# oled_control.net
KiCad netlist of a schematic drawn in Altium Designer
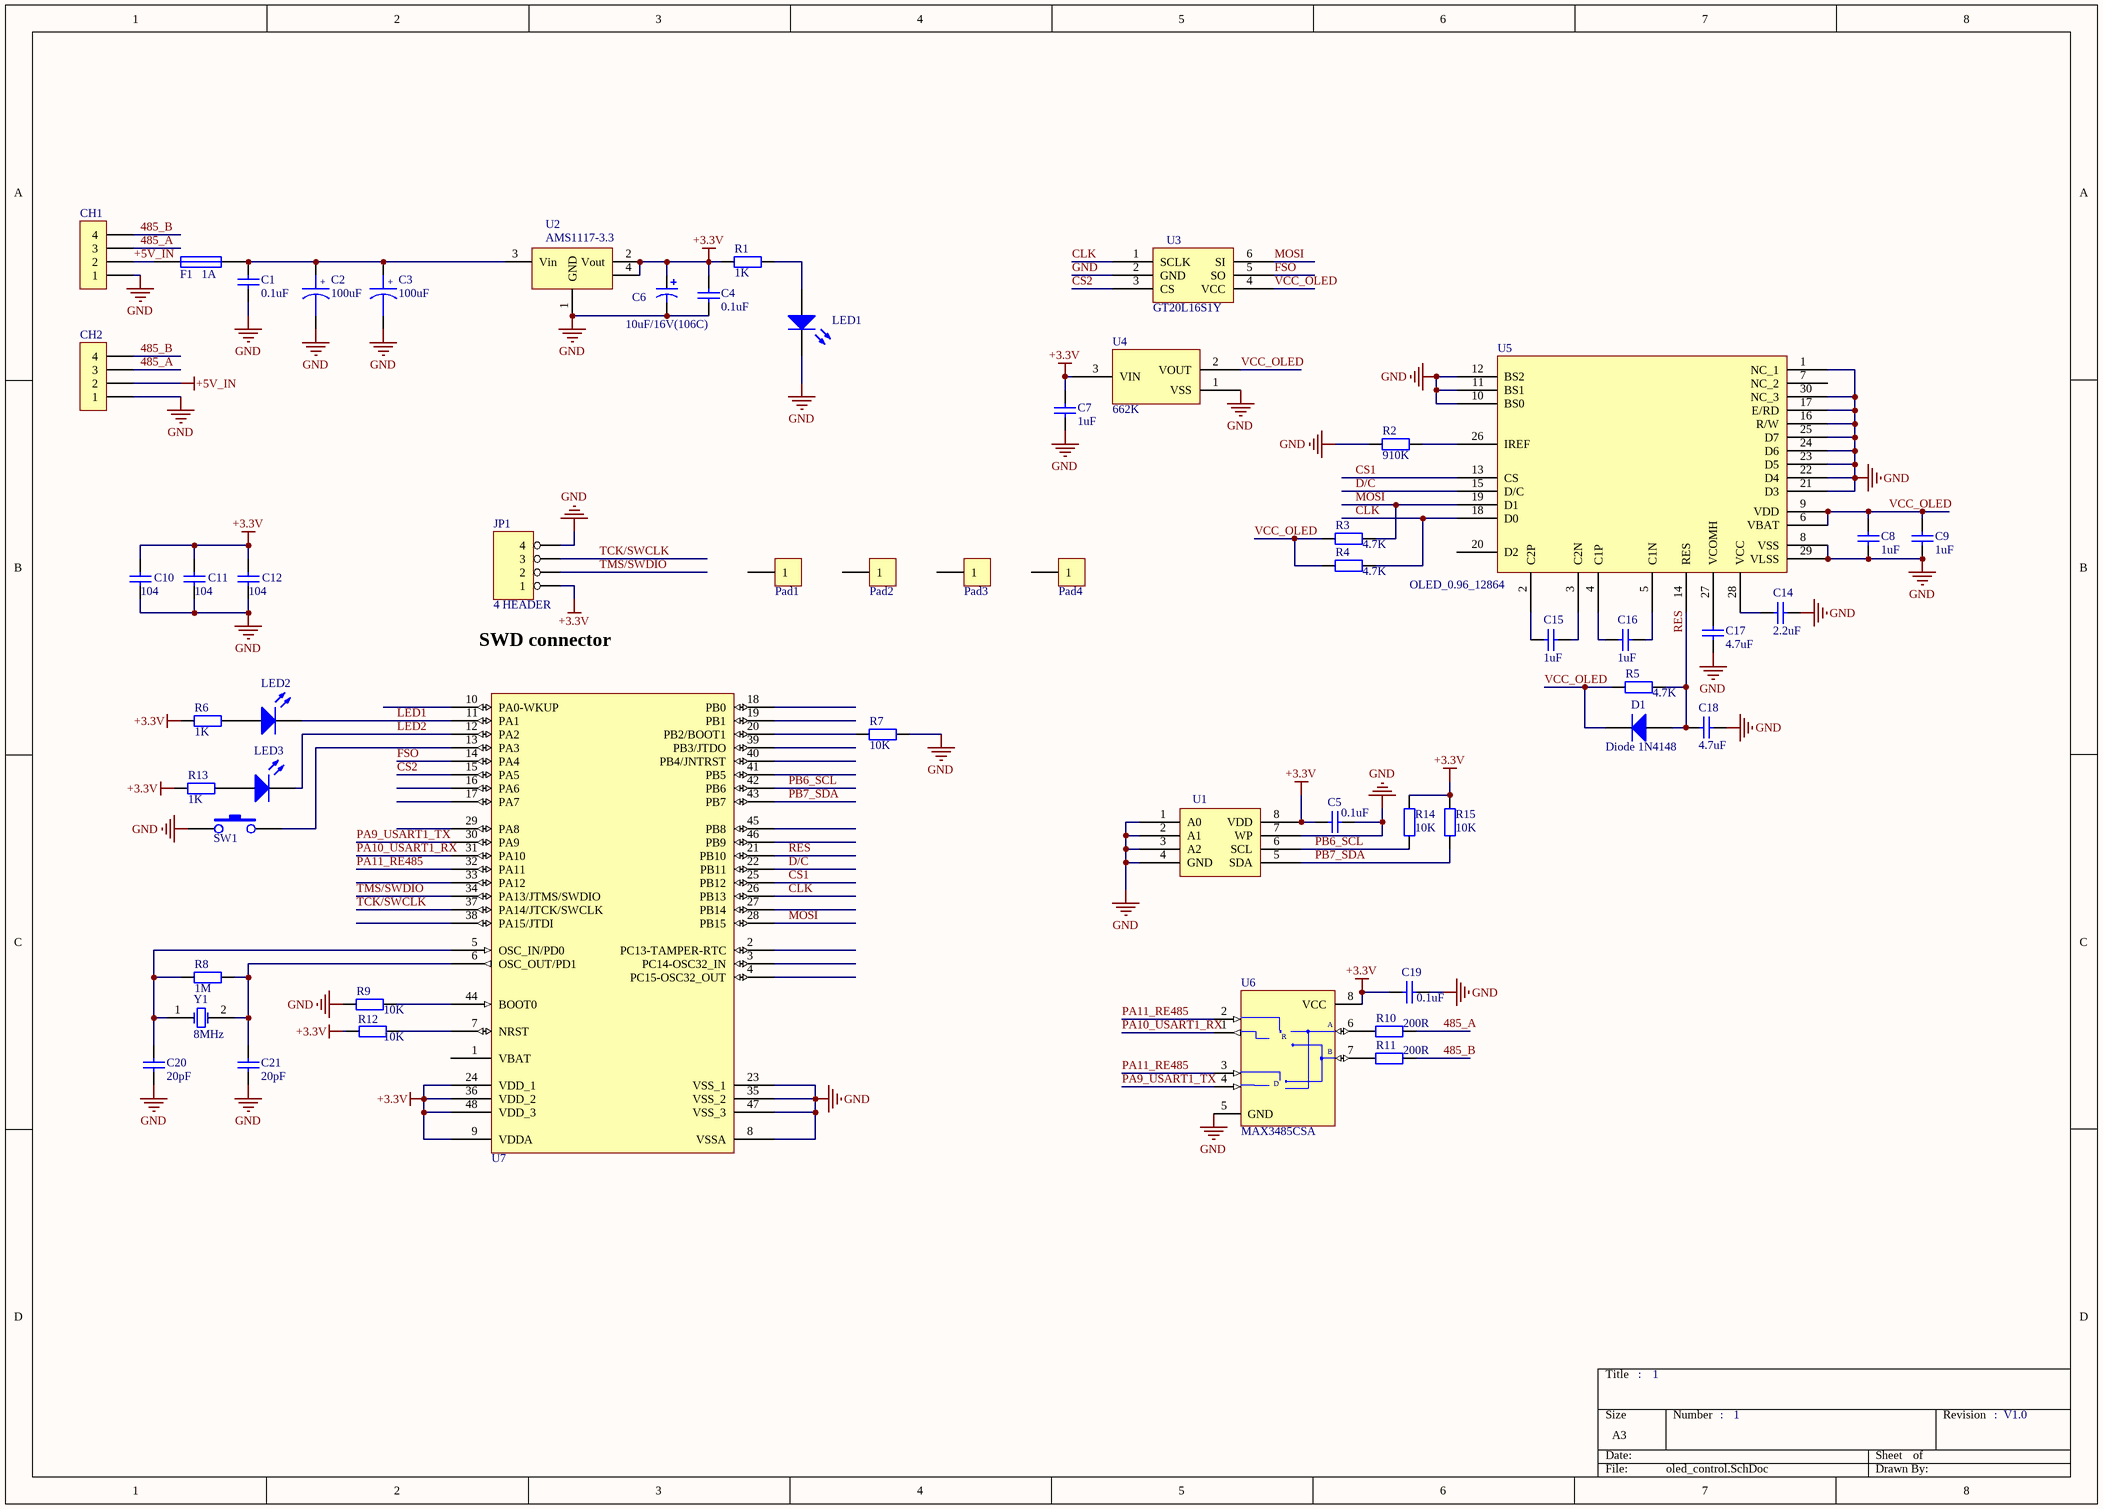
[diagram p0: oled_control.SchDoc]

(export (version "E")
  (design (tool "Eeschema 10.0.6"))
  (components
    (comp (ref "C1")
      (value "0.1uF")
      (footprint "0805")
      (description "Capacitor")
      (fields (field (name "Comment") "Cap") (field (name "PUBLISHER") "Altium Limited"))
      (libsource (lib "Miscellaneous Devices") (part "Cap"))
    )
    (comp (ref "C2")
      (value "C_2200uF")
      (footprint "B: 3528")
      (fields (field (name "ALTIUM_UNNAMED_1") "100uF"))
      (libsource (lib "myIntegrated_Library1") (part "C_2200uF"))
    )
    (comp (ref "C3")
      (value "C_2200uF")
      (footprint "B: 3528")
      (fields (field (name "ALTIUM_UNNAMED_1") "100uF"))
      (libsource (lib "myIntegrated_Library1") (part "C_2200uF"))
    )
    (comp (ref "C4")
      (value "0.1uF")
      (footprint "0805")
      (description "Capacitor")
      (fields (field (name "Comment") "Cap") (field (name "PUBLISHER") "Altium Limited"))
      (libsource (lib "Miscellaneous Devices") (part "Cap"))
    )
    (comp (ref "C5")
      (value "0.1uF")
      (footprint "0805")
      (description "Capacitor")
      (fields (field (name "Comment") "Cap") (field (name "PUBLISHER") "Altium Limited"))
      (libsource (lib "Miscellaneous Devices") (part "Cap"))
    )
    (comp (ref "C6")
      (value "10uF/16V(106C)")
      (footprint "CAP A-3216")
      (description "Polarized Capacitor (Surface Mount)")
      (fields (field (name "Comment") "Cap Pol3") (field (name "PUBLISHER") "Altium Limited"))
      (libsource (lib "Miscellaneous Devices") (part "Cap Pol3"))
    )
    (comp (ref "C7")
      (value "1uF")
      (footprint "0805")
      (description "Capacitor")
      (fields (field (name "Comment") "Cap") (field (name "PUBLISHER") "Altium Limited"))
      (libsource (lib "Miscellaneous Devices") (part "Cap"))
    )
    (comp (ref "C8")
      (value "1uF")
      (footprint "0805")
      (description "Capacitor")
      (fields (field (name "Comment") "Cap") (field (name "PUBLISHER") "Altium Limited"))
      (libsource (lib "Miscellaneous Devices") (part "Cap"))
    )
    (comp (ref "C9")
      (value "1uF")
      (footprint "0805")
      (description "Capacitor")
      (fields (field (name "Comment") "Cap") (field (name "PUBLISHER") "Altium Limited"))
      (libsource (lib "Miscellaneous Devices") (part "Cap"))
    )
    (comp (ref "C10")
      (value "104")
      (footprint "0805")
      (description "Capacitor")
      (fields (field (name "Comment") "Cap") (field (name "PUBLISHER") "Altium Limited"))
      (libsource (lib "Miscellaneous Devices") (part "Cap"))
    )
    (comp (ref "C11")
      (value "104")
      (footprint "0805")
      (description "Capacitor")
      (fields (field (name "Comment") "Cap") (field (name "PUBLISHER") "Altium Limited"))
      (libsource (lib "Miscellaneous Devices") (part "Cap"))
    )
    (comp (ref "C12")
      (value "104")
      (footprint "0805")
      (description "Capacitor")
      (fields (field (name "Comment") "Cap") (field (name "PUBLISHER") "Altium Limited"))
      (libsource (lib "Miscellaneous Devices") (part "Cap"))
    )
    (comp (ref "C14")
      (value "2.2uF")
      (footprint "0805")
      (description "Capacitor")
      (fields (field (name "Comment") "Cap") (field (name "PUBLISHER") "Altium Limited"))
      (libsource (lib "Miscellaneous Devices") (part "Cap"))
    )
    (comp (ref "C15")
      (value "1uF")
      (footprint "0805")
      (description "Capacitor")
      (fields (field (name "Comment") "Cap") (field (name "PUBLISHER") "Altium Limited"))
      (libsource (lib "Miscellaneous Devices") (part "Cap"))
    )
    (comp (ref "C16")
      (value "1uF")
      (footprint "0805")
      (description "Capacitor")
      (fields (field (name "Comment") "Cap") (field (name "PUBLISHER") "Altium Limited"))
      (libsource (lib "Miscellaneous Devices") (part "Cap"))
    )
    (comp (ref "C17")
      (value "4.7uF")
      (footprint "0805")
      (description "Capacitor")
      (fields (field (name "Comment") "Cap") (field (name "PUBLISHER") "Altium Limited"))
      (libsource (lib "Miscellaneous Devices") (part "Cap"))
    )
    (comp (ref "C18")
      (value "4.7uF")
      (footprint "0805")
      (description "Capacitor")
      (fields (field (name "Comment") "Cap") (field (name "PUBLISHER") "Altium Limited"))
      (libsource (lib "Miscellaneous Devices") (part "Cap"))
    )
    (comp (ref "C19")
      (value "0.1uF")
      (footprint "0805")
      (description "Capacitor")
      (fields (field (name "Comment") "Cap") (field (name "PUBLISHER") "Altium Limited"))
      (libsource (lib "Miscellaneous Devices") (part "Cap"))
    )
    (comp (ref "C20")
      (value "20pF")
      (footprint "0805")
      (description "Capacitor")
      (fields (field (name "Comment") "Cap") (field (name "PUBLISHER") "Altium Limited"))
      (libsource (lib "开发板元件库") (part "Cap"))
    )
    (comp (ref "C21")
      (value "20pF")
      (footprint "0805")
      (description "Capacitor")
      (fields (field (name "Comment") "Cap") (field (name "PUBLISHER") "Altium Limited"))
      (libsource (lib "开发板元件库") (part "Cap"))
    )
    (comp (ref "CH1")
      (value "HEADER1X4")
      (footprint "CON4_1.5")
      (libsource (lib "myIntegrated_Library1") (part "HEADER1X4"))
    )
    (comp (ref "CH2")
      (value "HEADER1X4")
      (footprint "CON4_1.5")
      (libsource (lib "myIntegrated_Library1") (part "HEADER1X4"))
    )
    (comp (ref "D1")
      (value "Diode 1N4148")
      (footprint "LL34")
      (description "High Conductance Fast Diode")
      (fields (field (name "PUBLISHER") "Altium Limited"))
      (libsource (lib "Miscellaneous Devices") (part "Diode 1N4148"))
    )
    (comp (ref "F1")
      (value "FUSE")
      (footprint "0805")
      (fields (field (name "ALTIUM_UNNAMED_1") "1A"))
      (libsource (lib "myIntegrated_Library1") (part "FUSE"))
    )
    (comp (ref "JP1")
      (value "4 HEADER")
      (footprint "CON4_1.5")
      (description "4 Pin Header")
      (libsource (lib "Miscellaneous Devices") (part "4 HEADER"))
    )
    (comp (ref "LED1")
      (value "~")
      (footprint "LED-0805")
      (description "Typical RED, GREEN, YELLOW, AMBER GaAs LED")
      (fields (field (name "PUBLISHER") "Altium Limited"))
      (libsource (lib "Miscellaneous Devices") (part "LED2"))
    )
    (comp (ref "LED2")
      (value "~")
      (footprint "LED-0805")
      (description "Typical RED, GREEN, YELLOW, AMBER GaAs LED")
      (fields (field (name "PUBLISHER") "Altium Limited"))
      (libsource (lib "Miscellaneous Devices") (part "LED2"))
    )
    (comp (ref "LED3")
      (value "~")
      (footprint "LED_5X5")
      (description "Typical RED, GREEN, YELLOW, AMBER GaAs LED")
      (fields (field (name "PUBLISHER") "Altium Limited"))
      (libsource (lib "Miscellaneous Devices") (part "LED2"))
    )
    (comp (ref "Pad1")
      (value "Pad")
      (footprint "pad35")
      (libsource (lib "myIntegrated_Library1") (part "Pad"))
    )
    (comp (ref "Pad2")
      (value "Pad")
      (footprint "pad35")
      (libsource (lib "myIntegrated_Library1") (part "Pad"))
    )
    (comp (ref "Pad3")
      (value "Pad")
      (footprint "pad35")
      (libsource (lib "myIntegrated_Library1") (part "Pad"))
    )
    (comp (ref "Pad4")
      (value "Pad")
      (footprint "pad35")
      (libsource (lib "myIntegrated_Library1") (part "Pad"))
    )
    (comp (ref "R1")
      (value "1K")
      (footprint "0805")
      (description "Resistor")
      (fields (field (name "Comment") "Res2") (field (name "PUBLISHER") "Altium Limited"))
      (libsource (lib "Miscellaneous Devices") (part "Res2"))
    )
    (comp (ref "R2")
      (value "910K")
      (footprint "0805")
      (description "Resistor")
      (fields (field (name "Comment") "Res2") (field (name "PUBLISHER") "Altium Limited"))
      (libsource (lib "Miscellaneous Devices") (part "Res2"))
    )
    (comp (ref "R3")
      (value "4.7K")
      (footprint "0805")
      (description "Resistor")
      (fields (field (name "Comment") "Res2") (field (name "PUBLISHER") "Altium Limited"))
      (libsource (lib "Miscellaneous Devices") (part "Res2"))
    )
    (comp (ref "R4")
      (value "4.7K")
      (footprint "0805")
      (description "Resistor")
      (fields (field (name "Comment") "Res2") (field (name "PUBLISHER") "Altium Limited"))
      (libsource (lib "Miscellaneous Devices") (part "Res2"))
    )
    (comp (ref "R5")
      (value "4.7K")
      (footprint "0805")
      (description "Resistor")
      (fields (field (name "Comment") "Res2") (field (name "PUBLISHER") "Altium Limited"))
      (libsource (lib "Miscellaneous Devices") (part "Res2"))
    )
    (comp (ref "R6")
      (value "1K")
      (footprint "0805")
      (description "Resistor")
      (fields (field (name "Comment") "Res2") (field (name "PUBLISHER") "Altium Limited"))
      (libsource (lib "Miscellaneous Devices") (part "Res2"))
    )
    (comp (ref "R7")
      (value "10K")
      (footprint "0805")
      (description "Resistor")
      (fields (field (name "Comment") "Res2") (field (name "PUBLISHER") "Altium Limited"))
      (libsource (lib "开发板元件库") (part "Res2"))
    )
    (comp (ref "R8")
      (value "1M")
      (footprint "0805")
      (description "Resistor")
      (fields (field (name "Comment") "Res2") (field (name "PUBLISHER") "Altium Limited"))
      (libsource (lib "开发板元件库") (part "Res2"))
    )
    (comp (ref "R9")
      (value "10K")
      (footprint "0805")
      (description "Resistor")
      (fields (field (name "Comment") "Res2") (field (name "PUBLISHER") "Altium Limited"))
      (libsource (lib "开发板元件库") (part "Res2"))
    )
    (comp (ref "R10")
      (value "200R")
      (footprint "0805")
      (description "Resistor")
      (fields (field (name "Comment") "Res2") (field (name "PUBLISHER") "Altium Limited"))
      (libsource (lib "") (part "Res2_1"))
    )
    (comp (ref "R11")
      (value "200R")
      (footprint "0805")
      (description "Resistor")
      (fields (field (name "Comment") "Res2") (field (name "PUBLISHER") "Altium Limited"))
      (libsource (lib "") (part "Res2_1"))
    )
    (comp (ref "R12")
      (value "10K")
      (footprint "0805")
      (description "Resistor")
      (fields (field (name "Comment") "Res2") (field (name "PUBLISHER") "Altium Limited"))
      (libsource (lib "开发板元件库") (part "Res2"))
    )
    (comp (ref "R13")
      (value "1K")
      (footprint "0805")
      (description "Resistor")
      (fields (field (name "Comment") "Res2") (field (name "PUBLISHER") "Altium Limited"))
      (libsource (lib "Miscellaneous Devices") (part "Res2"))
    )
    (comp (ref "R14")
      (value "10K")
      (footprint "C0805tan")
      (description "Resistor")
      (fields (field (name "Comment") "Res2") (field (name "PUBLISHER") "Altium Limited"))
      (libsource (lib "") (part "Res2_2"))
    )
    (comp (ref "R15")
      (value "10K")
      (footprint "C0805tan")
      (description "Resistor")
      (fields (field (name "Comment") "Res2") (field (name "PUBLISHER") "Altium Limited"))
      (libsource (lib "") (part "Res2_2"))
    )
    (comp (ref "SW1")
      (value "SW-KEY-2")
      (footprint "KEY_SOP4X4")
      (libsource (lib "myIntegrated_Library1") (part "SW-KEY-2"))
    )
    (comp (ref "U1")
      (value "AT24c02")
      (footprint "TSSOP8")
      (libsource (lib "myIntegrated_Library1") (part "TI24c02"))
    )
    (comp (ref "U2")
      (value "AMS1117-3.3")
      (footprint "SOT223")
      (libsource (lib "货架电子标签元件库") (part "AMS1117-5"))
    )
    (comp (ref "U3")
      (value "GT20L16S1Y")
      (footprint "SOT23-6")
      (libsource (lib "myIntegrated_Library1") (part "GT20L16S1Y"))
    )
    (comp (ref "U4")
      (value "662K")
      (footprint "SOT-23")
      (libsource (lib "myIntegrated_Library1") (part "662K"))
    )
    (comp (ref "U5")
      (value "OLED_0.96_12864")
      (footprint "OLED_1.30_12864")
      (libsource (lib "myIntegrated_Library1") (part "OLED_0.96_12864"))
    )
    (comp (ref "U6")
      (value "MAX3485CSA")
      (footprint "NS08-L")
      (libsource (lib "myIntegrated_Library1") (part "MAX485CSA"))
    )
    (comp (ref "U7")
      (value "STM32F103C8T6")
      (footprint "LQFP48")
      (libsource (lib "myIntegrated_Library1") (part "STM32F103C8T6"))
    )
    (comp (ref "Y1")
      (value "8MHz")
      (footprint "XTAL_US1")
      (description "Crystal Oscillator")
      (fields (field (name "PUBLISHER") "Altium Limited"))
      (libsource (lib "战舰STM32开发板底板封装库") (part "XTAL"))
    )
  )
  (nets
    (net (code "1") (name "+3.3V") (class "Default")
      (node (ref "C10") (pin "2") (pinfunction "2_2") (pintype "passive"))
      (node (ref "C11") (pin "2") (pinfunction "2_2") (pintype "passive"))
      (node (ref "C12") (pin "2") (pinfunction "2_2") (pintype "passive"))
      (node (ref "C19") (pin "1") (pinfunction "1_1") (pintype "passive"))
      (node (ref "C4") (pin "2") (pinfunction "2_2") (pintype "passive"))
      (node (ref "C5") (pin "2") (pinfunction "2_2") (pintype "passive"))
      (node (ref "C6") (pin "1") (pinfunction "1_1") (pintype "passive"))
      (node (ref "C7") (pin "1") (pinfunction "1_1") (pintype "passive"))
      (node (ref "JP1") (pin "1") (pinfunction "1_1") (pintype "passive"))
      (node (ref "R1") (pin "2") (pinfunction "2_2") (pintype "passive"))
      (node (ref "R12") (pin "1") (pinfunction "1_1") (pintype "passive"))
      (node (ref "R13") (pin "2") (pinfunction "2_2") (pintype "passive"))
      (node (ref "R14") (pin "2") (pinfunction "2_2") (pintype "passive"))
      (node (ref "R15") (pin "2") (pinfunction "2_2") (pintype "passive"))
      (node (ref "R6") (pin "2") (pinfunction "2_2") (pintype "passive"))
      (node (ref "U1") (pin "8") (pinfunction "VDD_8") (pintype "passive"))
      (node (ref "U2") (pin "2") (pinfunction "Vout_2") (pintype "passive"))
      (node (ref "U2") (pin "4") (pintype "passive"))
      (node (ref "U4") (pin "3") (pinfunction "VIN_3") (pintype "passive"))
      (node (ref "U6") (pin "8") (pinfunction "VCC_8") (pintype "power_in"))
      (node (ref "U7") (pin "24") (pinfunction "VDD_1_24") (pintype "power_in"))
      (node (ref "U7") (pin "36") (pinfunction "VDD_2_36") (pintype "power_in"))
      (node (ref "U7") (pin "48") (pinfunction "VDD_3_48") (pintype "power_in"))
      (node (ref "U7") (pin "9") (pinfunction "VDDA_9") (pintype "power_in"))
    )
    (net (code "2") (name "+5V_IN") (class "Default")
      (node (ref "CH1") (pin "2") (pinfunction "2_2") (pintype "passive"))
      (node (ref "CH2") (pin "2") (pinfunction "2_2") (pintype "passive"))
      (node (ref "F1") (pin "1") (pinfunction "1_1") (pintype "passive"))
    )
    (net (code "3") (name "/485_A") (class "Default")
      (node (ref "CH1") (pin "3") (pinfunction "3_3") (pintype "passive"))
      (node (ref "CH2") (pin "3") (pinfunction "3_3") (pintype "passive"))
      (node (ref "R10") (pin "2") (pinfunction "2_2") (pintype "passive"))
    )
    (net (code "4") (name "/485_B") (class "Default")
      (node (ref "CH1") (pin "4") (pinfunction "4_4") (pintype "passive"))
      (node (ref "CH2") (pin "4") (pinfunction "4_4") (pintype "passive"))
      (node (ref "R11") (pin "2") (pinfunction "2_2") (pintype "passive"))
    )
    (net (code "5") (name "/CLK") (class "Default")
      (node (ref "R4") (pin "1") (pinfunction "1_1") (pintype "passive"))
      (node (ref "U3") (pin "1") (pinfunction "SCLK_1") (pintype "passive"))
      (node (ref "U5") (pin "18") (pinfunction "D0_18") (pintype "passive"))
      (node (ref "U7") (pin "26") (pinfunction "PB13_26") (pintype "bidirectional"))
    )
    (net (code "6") (name "/CS1") (class "Default")
      (node (ref "U5") (pin "13") (pinfunction "CS_13") (pintype "passive"))
      (node (ref "U7") (pin "25") (pinfunction "PB12_25") (pintype "bidirectional"))
    )
    (net (code "7") (name "/CS2") (class "Default")
      (node (ref "U3") (pin "3") (pinfunction "CS_3") (pintype "passive"))
      (node (ref "U7") (pin "15") (pinfunction "PA5_15") (pintype "bidirectional"))
    )
    (net (code "8") (name "/D{slash}C") (class "Default")
      (node (ref "U5") (pin "15") (pinfunction "D/C_15") (pintype "passive"))
      (node (ref "U7") (pin "22") (pinfunction "PB11_22") (pintype "bidirectional"))
    )
    (net (code "9") (name "/FSO") (class "Default")
      (node (ref "U3") (pin "5") (pinfunction "SO_5") (pintype "passive"))
      (node (ref "U7") (pin "14") (pinfunction "PA4_14") (pintype "bidirectional"))
    )
    (net (code "10") (name "/LED1") (class "Default")
      (node (ref "LED2") (pin "2") (pinfunction "K_2") (pintype "passive"))
      (node (ref "U7") (pin "11") (pinfunction "PA1_11") (pintype "bidirectional"))
    )
    (net (code "11") (name "/LED2") (class "Default")
      (node (ref "LED3") (pin "2") (pinfunction "K_2") (pintype "passive"))
      (node (ref "U7") (pin "12") (pinfunction "PA2_12") (pintype "bidirectional"))
    )
    (net (code "12") (name "/MOSI") (class "Default")
      (node (ref "R3") (pin "1") (pinfunction "1_1") (pintype "passive"))
      (node (ref "U3") (pin "6") (pinfunction "SI_6") (pintype "passive"))
      (node (ref "U5") (pin "19") (pinfunction "D1_19") (pintype "passive"))
      (node (ref "U7") (pin "28") (pinfunction "PB15_28") (pintype "bidirectional"))
    )
    (net (code "13") (name "/PA9_USART1_TX") (class "Default")
      (node (ref "U6") (pin "4") (pinfunction "DI_4") (pintype "input"))
      (node (ref "U7") (pin "30") (pinfunction "PA9_30") (pintype "bidirectional"))
    )
    (net (code "14") (name "/PA10_USART1_RX") (class "Default")
      (node (ref "U6") (pin "1") (pinfunction "RO_1") (pintype "output"))
      (node (ref "U7") (pin "31") (pinfunction "PA10_31") (pintype "bidirectional"))
    )
    (net (code "15") (name "/PA11_RE485") (class "Default")
      (node (ref "U6") (pin "2") (pinfunction "~{RE}_2") (pintype "input"))
      (node (ref "U6") (pin "3") (pinfunction "DE_3") (pintype "input"))
      (node (ref "U7") (pin "32") (pinfunction "PA11_32") (pintype "bidirectional"))
    )
    (net (code "16") (name "/PB6_SCL") (class "Default")
      (node (ref "R14") (pin "1") (pinfunction "1_1") (pintype "passive"))
      (node (ref "U1") (pin "6") (pinfunction "SCL_6") (pintype "passive"))
      (node (ref "U7") (pin "42") (pinfunction "PB6_42") (pintype "bidirectional"))
    )
    (net (code "17") (name "/PB7_SDA") (class "Default")
      (node (ref "R15") (pin "1") (pinfunction "1_1") (pintype "passive"))
      (node (ref "U1") (pin "5") (pinfunction "SDA_5") (pintype "passive"))
      (node (ref "U7") (pin "43") (pinfunction "PB7_43") (pintype "bidirectional"))
    )
    (net (code "18") (name "/RES") (class "Default")
      (node (ref "C18") (pin "2") (pinfunction "2_2") (pintype "passive"))
      (node (ref "D1") (pin "1") (pinfunction "A_1") (pintype "passive"))
      (node (ref "R5") (pin "1") (pinfunction "1_1") (pintype "passive"))
      (node (ref "U5") (pin "14") (pinfunction "RES_14") (pintype "passive"))
      (node (ref "U7") (pin "21") (pinfunction "PB10_21") (pintype "bidirectional"))
    )
    (net (code "19") (name "/TCK{slash}SWCLK") (class "Default")
      (node (ref "JP1") (pin "3") (pinfunction "3_3") (pintype "passive"))
      (node (ref "U7") (pin "37") (pinfunction "PA14/JTCK/SWCLK_37") (pintype "bidirectional"))
    )
    (net (code "20") (name "/TMS{slash}SWDIO") (class "Default")
      (node (ref "JP1") (pin "2") (pinfunction "2_2") (pintype "passive"))
      (node (ref "U7") (pin "34") (pinfunction "PA13/JTMS/SWDIO_34") (pintype "bidirectional"))
    )
    (net (code "21") (name "/VCC_OLED") (class "Default")
      (node (ref "C8") (pin "1") (pinfunction "1_1") (pintype "passive"))
      (node (ref "C9") (pin "1") (pinfunction "1_1") (pintype "passive"))
      (node (ref "D1") (pin "2") (pinfunction "K_2") (pintype "passive"))
      (node (ref "R3") (pin "2") (pinfunction "2_2") (pintype "passive"))
      (node (ref "R4") (pin "2") (pinfunction "2_2") (pintype "passive"))
      (node (ref "R5") (pin "2") (pinfunction "2_2") (pintype "passive"))
      (node (ref "U3") (pin "4") (pinfunction "VCC_4") (pintype "passive"))
      (node (ref "U4") (pin "2") (pinfunction "VOUT_2") (pintype "passive"))
      (node (ref "U5") (pin "6") (pinfunction "VBAT_6") (pintype "passive"))
      (node (ref "U5") (pin "9") (pinfunction "VDD_9") (pintype "passive"))
    )
    (net (code "22") (name "GND") (class "Default")
      (node (ref "C1") (pin "1") (pinfunction "1_1") (pintype "passive"))
      (node (ref "C10") (pin "1") (pinfunction "1_1") (pintype "passive"))
      (node (ref "C11") (pin "1") (pinfunction "1_1") (pintype "passive"))
      (node (ref "C12") (pin "1") (pinfunction "1_1") (pintype "passive"))
      (node (ref "C14") (pin "1") (pinfunction "1_1") (pintype "passive"))
      (node (ref "C17") (pin "2") (pinfunction "2_2") (pintype "passive"))
      (node (ref "C18") (pin "1") (pinfunction "1_1") (pintype "passive"))
      (node (ref "C19") (pin "2") (pinfunction "2_2") (pintype "passive"))
      (node (ref "C2") (pin "2") (pinfunction "2_2") (pintype "passive"))
      (node (ref "C20") (pin "1") (pinfunction "1_1") (pintype "passive"))
      (node (ref "C21") (pin "1") (pinfunction "1_1") (pintype "passive"))
      (node (ref "C3") (pin "2") (pinfunction "2_2") (pintype "passive"))
      (node (ref "C4") (pin "1") (pinfunction "1_1") (pintype "passive"))
      (node (ref "C5") (pin "1") (pinfunction "1_1") (pintype "passive"))
      (node (ref "C6") (pin "2") (pinfunction "2_2") (pintype "passive"))
      (node (ref "C7") (pin "2") (pinfunction "2_2") (pintype "passive"))
      (node (ref "C8") (pin "2") (pinfunction "2_2") (pintype "passive"))
      (node (ref "C9") (pin "2") (pinfunction "2_2") (pintype "passive"))
      (node (ref "CH1") (pin "1") (pinfunction "1_1") (pintype "passive"))
      (node (ref "CH2") (pin "1") (pinfunction "1_1") (pintype "passive"))
      (node (ref "JP1") (pin "4") (pinfunction "4_4") (pintype "passive"))
      (node (ref "LED1") (pin "2") (pinfunction "K_2") (pintype "passive"))
      (node (ref "R2") (pin "2") (pinfunction "2_2") (pintype "passive"))
      (node (ref "R7") (pin "2") (pinfunction "2_2") (pintype "passive"))
      (node (ref "R9") (pin "1") (pinfunction "1_1") (pintype "passive"))
      (node (ref "SW1") (pin "1") (pinfunction "1_1") (pintype "passive"))
      (node (ref "U1") (pin "1") (pinfunction "A0_1") (pintype "passive"))
      (node (ref "U1") (pin "2") (pinfunction "A1_2") (pintype "passive"))
      (node (ref "U1") (pin "3") (pinfunction "A2_3") (pintype "passive"))
      (node (ref "U1") (pin "4") (pinfunction "GND_4") (pintype "passive"))
      (node (ref "U1") (pin "7") (pinfunction "WP_7") (pintype "passive"))
      (node (ref "U2") (pin "1") (pinfunction "GND_1") (pintype "passive"))
      (node (ref "U3") (pin "2") (pinfunction "GND_2") (pintype "passive"))
      (node (ref "U4") (pin "1") (pinfunction "VSS_1") (pintype "passive"))
      (node (ref "U5") (pin "1") (pinfunction "NC_1_1") (pintype "passive"))
      (node (ref "U5") (pin "10") (pinfunction "BS0_10") (pintype "passive"))
      (node (ref "U5") (pin "11") (pinfunction "BS1_11") (pintype "passive"))
      (node (ref "U5") (pin "12") (pinfunction "BS2_12") (pintype "passive"))
      (node (ref "U5") (pin "16") (pinfunction "R/W_16") (pintype "passive"))
      (node (ref "U5") (pin "17") (pinfunction "E/RD_17") (pintype "passive"))
      (node (ref "U5") (pin "21") (pinfunction "D3_21") (pintype "passive"))
      (node (ref "U5") (pin "22") (pinfunction "D4_22") (pintype "passive"))
      (node (ref "U5") (pin "23") (pinfunction "D5_23") (pintype "passive"))
      (node (ref "U5") (pin "24") (pinfunction "D6_24") (pintype "passive"))
      (node (ref "U5") (pin "25") (pinfunction "D7_25") (pintype "passive"))
      (node (ref "U5") (pin "29") (pinfunction "VLSS_29") (pintype "passive"))
      (node (ref "U5") (pin "30") (pinfunction "NC_3_30") (pintype "passive"))
      (node (ref "U5") (pin "8") (pinfunction "VSS_8") (pintype "passive"))
      (node (ref "U6") (pin "5") (pinfunction "GND_5") (pintype "power_in"))
      (node (ref "U7") (pin "23") (pinfunction "VSS_1_23") (pintype "power_in"))
      (node (ref "U7") (pin "35") (pinfunction "VSS_2_35") (pintype "power_in"))
      (node (ref "U7") (pin "47") (pinfunction "VSS_3_47") (pintype "power_in"))
      (node (ref "U7") (pin "8") (pinfunction "VSSA_8") (pintype "power_in"))
    )
    (net (code "23") (name "Net-(LED1-A)") (class "Default")
      (node (ref "LED1") (pin "1") (pinfunction "A_1") (pintype "passive"))
      (node (ref "R1") (pin "1") (pinfunction "1_1") (pintype "passive"))
    )
    (net (code "24") (name "Net-(LED2-A)") (class "Default")
      (node (ref "LED2") (pin "1") (pinfunction "A_1") (pintype "passive"))
      (node (ref "R6") (pin "1") (pinfunction "1_1") (pintype "passive"))
    )
    (net (code "25") (name "Net-(LED3-A)") (class "Default")
      (node (ref "LED3") (pin "1") (pinfunction "A_1") (pintype "passive"))
      (node (ref "R13") (pin "1") (pinfunction "1_1") (pintype "passive"))
    )
    (net (code "26") (name "Net-(U2-Vin)") (class "Default")
      (node (ref "C1") (pin "2") (pinfunction "2_2") (pintype "passive"))
      (node (ref "C2") (pin "1") (pinfunction "1_1") (pintype "passive"))
      (node (ref "C3") (pin "1") (pinfunction "1_1") (pintype "passive"))
      (node (ref "F1") (pin "2") (pinfunction "2_2") (pintype "passive"))
      (node (ref "U2") (pin "3") (pinfunction "Vin_3") (pintype "passive"))
    )
    (net (code "27") (name "Net-(U5-C1N)") (class "Default")
      (node (ref "C16") (pin "1") (pinfunction "1_1") (pintype "passive"))
      (node (ref "U5") (pin "5") (pinfunction "C1N_5") (pintype "passive"))
    )
    (net (code "28") (name "Net-(U5-C1P)") (class "Default")
      (node (ref "C16") (pin "2") (pinfunction "2_2") (pintype "passive"))
      (node (ref "U5") (pin "4") (pinfunction "C1P_4") (pintype "passive"))
    )
    (net (code "29") (name "Net-(U5-C2N)") (class "Default")
      (node (ref "C15") (pin "1") (pinfunction "1_1") (pintype "passive"))
      (node (ref "U5") (pin "3") (pinfunction "C2N_3") (pintype "passive"))
    )
    (net (code "30") (name "Net-(U5-C2P)") (class "Default")
      (node (ref "C15") (pin "2") (pinfunction "2_2") (pintype "passive"))
      (node (ref "U5") (pin "2") (pinfunction "C2P_2") (pintype "passive"))
    )
    (net (code "31") (name "Net-(U5-IREF)") (class "Default")
      (node (ref "R2") (pin "1") (pinfunction "1_1") (pintype "passive"))
      (node (ref "U5") (pin "26") (pinfunction "IREF_26") (pintype "passive"))
    )
    (net (code "32") (name "Net-(U5-VCC)") (class "Default")
      (node (ref "C14") (pin "2") (pinfunction "2_2") (pintype "passive"))
      (node (ref "U5") (pin "28") (pinfunction "VCC_28") (pintype "passive"))
    )
    (net (code "33") (name "Net-(U5-VCOMH)") (class "Default")
      (node (ref "C17") (pin "1") (pinfunction "1_1") (pintype "passive"))
      (node (ref "U5") (pin "27") (pinfunction "VCOMH_27") (pintype "passive"))
    )
    (net (code "34") (name "Net-(U6-A)") (class "Default")
      (node (ref "R10") (pin "1") (pinfunction "1_1") (pintype "passive"))
      (node (ref "U6") (pin "6") (pinfunction "A_6") (pintype "bidirectional"))
    )
    (net (code "35") (name "Net-(U6-B)") (class "Default")
      (node (ref "R11") (pin "1") (pinfunction "1_1") (pintype "passive"))
      (node (ref "U6") (pin "7") (pinfunction "B_7") (pintype "bidirectional"))
    )
    (net (code "36") (name "Net-(U7-BOOT0)") (class "Default")
      (node (ref "R9") (pin "2") (pinfunction "2_2") (pintype "passive"))
      (node (ref "U7") (pin "44") (pinfunction "BOOT0_44") (pintype "input"))
    )
    (net (code "37") (name "Net-(U7-NRST)") (class "Default")
      (node (ref "R12") (pin "2") (pinfunction "2_2") (pintype "passive"))
      (node (ref "U7") (pin "7") (pinfunction "NRST_7") (pintype "bidirectional"))
    )
    (net (code "38") (name "Net-(U7-OSC_IN{slash}PD0)") (class "Default")
      (node (ref "C20") (pin "2") (pinfunction "2_2") (pintype "passive"))
      (node (ref "R8") (pin "1") (pinfunction "1_1") (pintype "passive"))
      (node (ref "U7") (pin "5") (pinfunction "OSC_IN/PD0_5") (pintype "input"))
      (node (ref "Y1") (pin "1") (pinfunction "OSC1_1") (pintype "passive"))
    )
    (net (code "39") (name "Net-(U7-OSC_OUT{slash}PD1)") (class "Default")
      (node (ref "C21") (pin "2") (pinfunction "2_2") (pintype "passive"))
      (node (ref "R8") (pin "2") (pinfunction "2_2") (pintype "passive"))
      (node (ref "U7") (pin "6") (pinfunction "OSC_OUT/PD1_6") (pintype "output"))
      (node (ref "Y1") (pin "2") (pinfunction "OSC2_2") (pintype "passive"))
    )
    (net (code "40") (name "Net-(U7-PA3)") (class "Default")
      (node (ref "SW1") (pin "2") (pinfunction "2_2") (pintype "passive"))
      (node (ref "U7") (pin "13") (pinfunction "PA3_13") (pintype "bidirectional"))
    )
    (net (code "41") (name "Net-(U7-PB2{slash}BOOT1)") (class "Default")
      (node (ref "R7") (pin "1") (pinfunction "1_1") (pintype "passive"))
      (node (ref "U7") (pin "20") (pinfunction "PB2/BOOT1_20") (pintype "bidirectional"))
    )
    (net (code "42") (name "unconnected-(Pad1-Pad1)") (class "Default")
      (node (ref "Pad1") (pin "1") (pinfunction "1_1") (pintype "passive"))
    )
    (net (code "43") (name "unconnected-(Pad2-Pad1)") (class "Default")
      (node (ref "Pad2") (pin "1") (pinfunction "1_1") (pintype "passive"))
    )
    (net (code "44") (name "unconnected-(Pad3-Pad1)") (class "Default")
      (node (ref "Pad3") (pin "1") (pinfunction "1_1") (pintype "passive"))
    )
    (net (code "45") (name "unconnected-(Pad4-Pad1)") (class "Default")
      (node (ref "Pad4") (pin "1") (pinfunction "1_1") (pintype "passive"))
    )
    (net (code "46") (name "unconnected-(U5-D2-Pad20)") (class "Default")
      (node (ref "U5") (pin "20") (pinfunction "D2_20") (pintype "passive"))
    )
    (net (code "47") (name "unconnected-(U5-NC_2-Pad7)") (class "Default")
      (node (ref "U5") (pin "7") (pinfunction "NC_2_7") (pintype "passive"))
    )
    (net (code "48") (name "unconnected-(U7-PA0-WKUP-Pad10)") (class "Default")
      (node (ref "U7") (pin "10") (pinfunction "PA0-WKUP_10") (pintype "bidirectional"))
    )
    (net (code "49") (name "unconnected-(U7-PA6-Pad16)") (class "Default")
      (node (ref "U7") (pin "16") (pinfunction "PA6_16") (pintype "bidirectional"))
    )
    (net (code "50") (name "unconnected-(U7-PA7-Pad17)") (class "Default")
      (node (ref "U7") (pin "17") (pinfunction "PA7_17") (pintype "bidirectional"))
    )
    (net (code "51") (name "unconnected-(U7-PA8-Pad29)") (class "Default")
      (node (ref "U7") (pin "29") (pinfunction "PA8_29") (pintype "bidirectional"))
    )
    (net (code "52") (name "unconnected-(U7-PA12-Pad33)") (class "Default")
      (node (ref "U7") (pin "33") (pinfunction "PA12_33") (pintype "bidirectional"))
    )
    (net (code "53") (name "unconnected-(U7-PA15{slash}JTDI-Pad38)") (class "Default")
      (node (ref "U7") (pin "38") (pinfunction "PA15/JTDI_38") (pintype "bidirectional"))
    )
    (net (code "54") (name "unconnected-(U7-PB0-Pad18)") (class "Default")
      (node (ref "U7") (pin "18") (pinfunction "PB0_18") (pintype "bidirectional"))
    )
    (net (code "55") (name "unconnected-(U7-PB1-Pad19)") (class "Default")
      (node (ref "U7") (pin "19") (pinfunction "PB1_19") (pintype "bidirectional"))
    )
    (net (code "56") (name "unconnected-(U7-PB3{slash}JTDO-Pad39)") (class "Default")
      (node (ref "U7") (pin "39") (pinfunction "PB3/JTDO_39") (pintype "bidirectional"))
    )
    (net (code "57") (name "unconnected-(U7-PB4{slash}JNTRST-Pad40)") (class "Default")
      (node (ref "U7") (pin "40") (pinfunction "PB4/JNTRST_40") (pintype "bidirectional"))
    )
    (net (code "58") (name "unconnected-(U7-PB5-Pad41)") (class "Default")
      (node (ref "U7") (pin "41") (pinfunction "PB5_41") (pintype "bidirectional"))
    )
    (net (code "59") (name "unconnected-(U7-PB8-Pad45)") (class "Default")
      (node (ref "U7") (pin "45") (pinfunction "PB8_45") (pintype "bidirectional"))
    )
    (net (code "60") (name "unconnected-(U7-PB9-Pad46)") (class "Default")
      (node (ref "U7") (pin "46") (pinfunction "PB9_46") (pintype "bidirectional"))
    )
    (net (code "61") (name "unconnected-(U7-PB14-Pad27)") (class "Default")
      (node (ref "U7") (pin "27") (pinfunction "PB14_27") (pintype "bidirectional"))
    )
    (net (code "62") (name "unconnected-(U7-PC13-TAMPER-RTC-Pad2)") (class "Default")
      (node (ref "U7") (pin "2") (pinfunction "PC13-TAMPER-RTC_2") (pintype "bidirectional"))
    )
    (net (code "63") (name "unconnected-(U7-PC14-OSC32_IN-Pad3)") (class "Default")
      (node (ref "U7") (pin "3") (pinfunction "PC14-OSC32_IN_3") (pintype "bidirectional"))
    )
    (net (code "64") (name "unconnected-(U7-PC15-OSC32_OUT-Pad4)") (class "Default")
      (node (ref "U7") (pin "4") (pinfunction "PC15-OSC32_OUT_4") (pintype "bidirectional"))
    )
    (net (code "65") (name "unconnected-(U7-VBAT-Pad1)") (class "Default")
      (node (ref "U7") (pin "1") (pinfunction "VBAT_1") (pintype "power_in"))
    )
  )
)
